# XBee_Sensor.net
KiCad netlist of a schematic drawn in EAGLE
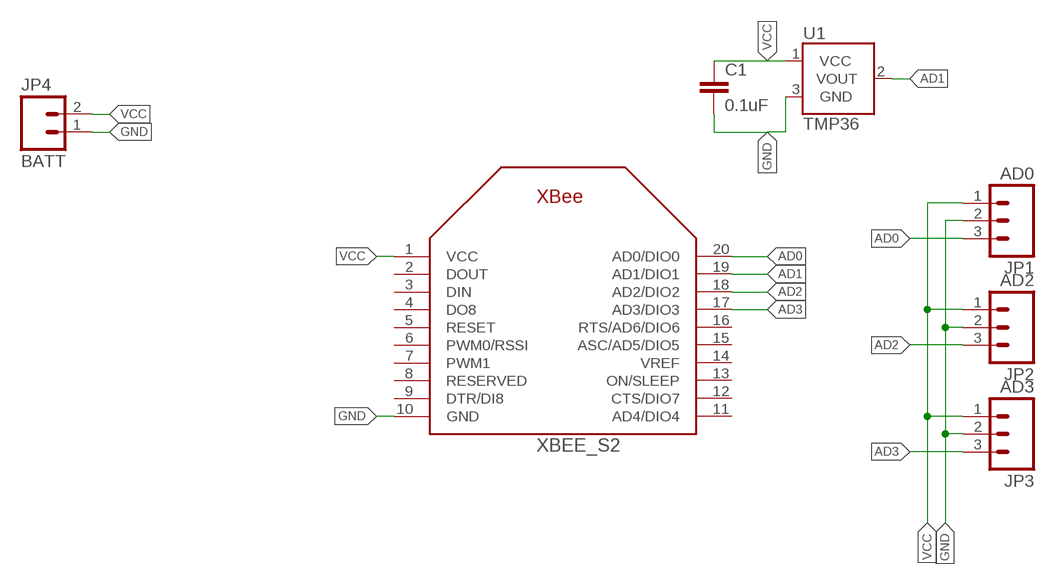
[diagram p0: schematic, sheet 1]

(export (version "E")
  (design (tool "Eeschema 10.0.6"))
  (components
    (comp (ref "C1")
      (value "0.1uF")
      (footprint "eagle-import:C050-035X075")
      (libsource (lib "eagle-import") (part "C-EU050-035X075"))
    )
    (comp (ref "JP1")
      (value "AD0")
      (footprint "eagle-import:JST-3-PTH")
      (libsource (lib "eagle-import") (part "M03JST-PTH"))
    )
    (comp (ref "JP2")
      (value "AD2")
      (footprint "eagle-import:JST-3-PTH")
      (libsource (lib "eagle-import") (part "M03JST-PTH"))
    )
    (comp (ref "JP3")
      (value "AD3")
      (footprint "eagle-import:JST-3-PTH")
      (libsource (lib "eagle-import") (part "M03JST-PTH"))
    )
    (comp (ref "JP4")
      (value "BATT")
      (footprint "eagle-import:JST-2-PTH")
      (libsource (lib "eagle-import") (part "M02JST-PTH-2"))
    )
    (comp (ref "U1")
      (value "TMP36")
      (footprint "eagle-import:TO-92-AMMO")
      (libsource (lib "eagle-import") (part "TMP36"))
    )
    (comp (ref "XBEE_S2")
      (value "XBEE")
      (footprint "eagle-import:XBEE")
      (libsource (lib "eagle-import") (part "XBEE"))
    )
  )
  (nets
    (net (code "1") (name "AD0") (class "Default")
      (node (ref "JP1") (pin "3") (pinfunction "3_3") (pintype "passive"))
      (node (ref "XBEE_S2") (pin "20") (pinfunction "AD0/DIO0_20") (pintype "bidirectional"))
    )
    (net (code "2") (name "AD1") (class "Default")
      (node (ref "U1") (pin "2") (pinfunction "VOUT_2") (pintype "bidirectional"))
      (node (ref "XBEE_S2") (pin "19") (pinfunction "AD1/DIO1_19") (pintype "bidirectional"))
    )
    (net (code "3") (name "AD2") (class "Default")
      (node (ref "JP2") (pin "3") (pinfunction "3_3") (pintype "passive"))
      (node (ref "XBEE_S2") (pin "18") (pinfunction "AD2/DIO2_18") (pintype "bidirectional"))
    )
    (net (code "4") (name "AD3") (class "Default")
      (node (ref "JP3") (pin "3") (pinfunction "3_3") (pintype "passive"))
      (node (ref "XBEE_S2") (pin "17") (pinfunction "AD3/DIO3_17") (pintype "bidirectional"))
    )
    (net (code "5") (name "GND") (class "Default")
      (node (ref "C1") (pin "2") (pinfunction "2_2") (pintype "passive"))
      (node (ref "JP1") (pin "2") (pinfunction "2_2") (pintype "passive"))
      (node (ref "JP2") (pin "2") (pinfunction "2_2") (pintype "passive"))
      (node (ref "JP3") (pin "2") (pinfunction "2_2") (pintype "passive"))
      (node (ref "JP4") (pin "1") (pinfunction "1_1") (pintype "passive"))
      (node (ref "U1") (pin "3") (pinfunction "GND_3") (pintype "bidirectional"))
      (node (ref "XBEE_S2") (pin "10") (pinfunction "GND_10") (pintype "power_in"))
    )
    (net (code "6") (name "VCC") (class "Default")
      (node (ref "C1") (pin "1") (pinfunction "1_1") (pintype "passive"))
      (node (ref "JP1") (pin "1") (pinfunction "1_1") (pintype "passive"))
      (node (ref "JP2") (pin "1") (pinfunction "1_1") (pintype "passive"))
      (node (ref "JP3") (pin "1") (pinfunction "1_1") (pintype "passive"))
      (node (ref "JP4") (pin "2") (pinfunction "2_2") (pintype "passive"))
      (node (ref "U1") (pin "1") (pinfunction "VCC_1") (pintype "bidirectional"))
      (node (ref "XBEE_S2") (pin "1") (pinfunction "VCC_1") (pintype "power_in"))
    )
    (net (code "7") (name "unconnected-(XBEE_S2-AD4{slash}DIO4-Pad11)") (class "Default")
      (node (ref "XBEE_S2") (pin "11") (pinfunction "AD4/DIO4_11") (pintype "bidirectional"))
    )
    (net (code "8") (name "unconnected-(XBEE_S2-ASC{slash}AD5{slash}DIO5-Pad15)") (class "Default")
      (node (ref "XBEE_S2") (pin "15") (pinfunction "ASC/AD5/DIO5_15") (pintype "bidirectional"))
    )
    (net (code "9") (name "unconnected-(XBEE_S2-CTS{slash}DIO7-Pad12)") (class "Default")
      (node (ref "XBEE_S2") (pin "12") (pinfunction "CTS/DIO7_12") (pintype "bidirectional"))
    )
    (net (code "10") (name "unconnected-(XBEE_S2-DIN-Pad3)") (class "Default")
      (node (ref "XBEE_S2") (pin "3") (pinfunction "DIN_3") (pintype "input"))
    )
    (net (code "11") (name "unconnected-(XBEE_S2-DO8-Pad4)") (class "Default")
      (node (ref "XBEE_S2") (pin "4") (pinfunction "DO8_4") (pintype "output"))
    )
    (net (code "12") (name "unconnected-(XBEE_S2-DOUT-Pad2)") (class "Default")
      (node (ref "XBEE_S2") (pin "2") (pinfunction "DOUT_2") (pintype "output"))
    )
    (net (code "13") (name "unconnected-(XBEE_S2-DTR{slash}DI8-Pad9)") (class "Default")
      (node (ref "XBEE_S2") (pin "9") (pinfunction "DTR/DI8_9") (pintype "input"))
    )
    (net (code "14") (name "unconnected-(XBEE_S2-ON{slash}SLEEP-Pad13)") (class "Default")
      (node (ref "XBEE_S2") (pin "13") (pinfunction "ON/SLEEP_13") (pintype "output"))
    )
    (net (code "15") (name "unconnected-(XBEE_S2-PWM0{slash}RSSI-Pad6)") (class "Default")
      (node (ref "XBEE_S2") (pin "6") (pinfunction "PWM0/RSSI_6") (pintype "output"))
    )
    (net (code "16") (name "unconnected-(XBEE_S2-PWM1-Pad7)") (class "Default")
      (node (ref "XBEE_S2") (pin "7") (pinfunction "PWM1_7") (pintype "output"))
    )
    (net (code "17") (name "unconnected-(XBEE_S2-RESERVED-Pad8)") (class "Default")
      (node (ref "XBEE_S2") (pin "8") (pinfunction "RESERVED_8") (pintype "no_connect"))
    )
    (net (code "18") (name "unconnected-(XBEE_S2-RESET-Pad5)") (class "Default")
      (node (ref "XBEE_S2") (pin "5") (pinfunction "RESET_5") (pintype "input"))
    )
    (net (code "19") (name "unconnected-(XBEE_S2-RTS{slash}AD6{slash}DIO6-Pad16)") (class "Default")
      (node (ref "XBEE_S2") (pin "16") (pinfunction "RTS/AD6/DIO6_16") (pintype "bidirectional"))
    )
    (net (code "20") (name "unconnected-(XBEE_S2-VREF-Pad14)") (class "Default")
      (node (ref "XBEE_S2") (pin "14") (pinfunction "VREF_14") (pintype "input"))
    )
  )
)
